# 17_Voltage_Regulators.net
KiCad netlist of a schematic drawn in Altium Designer
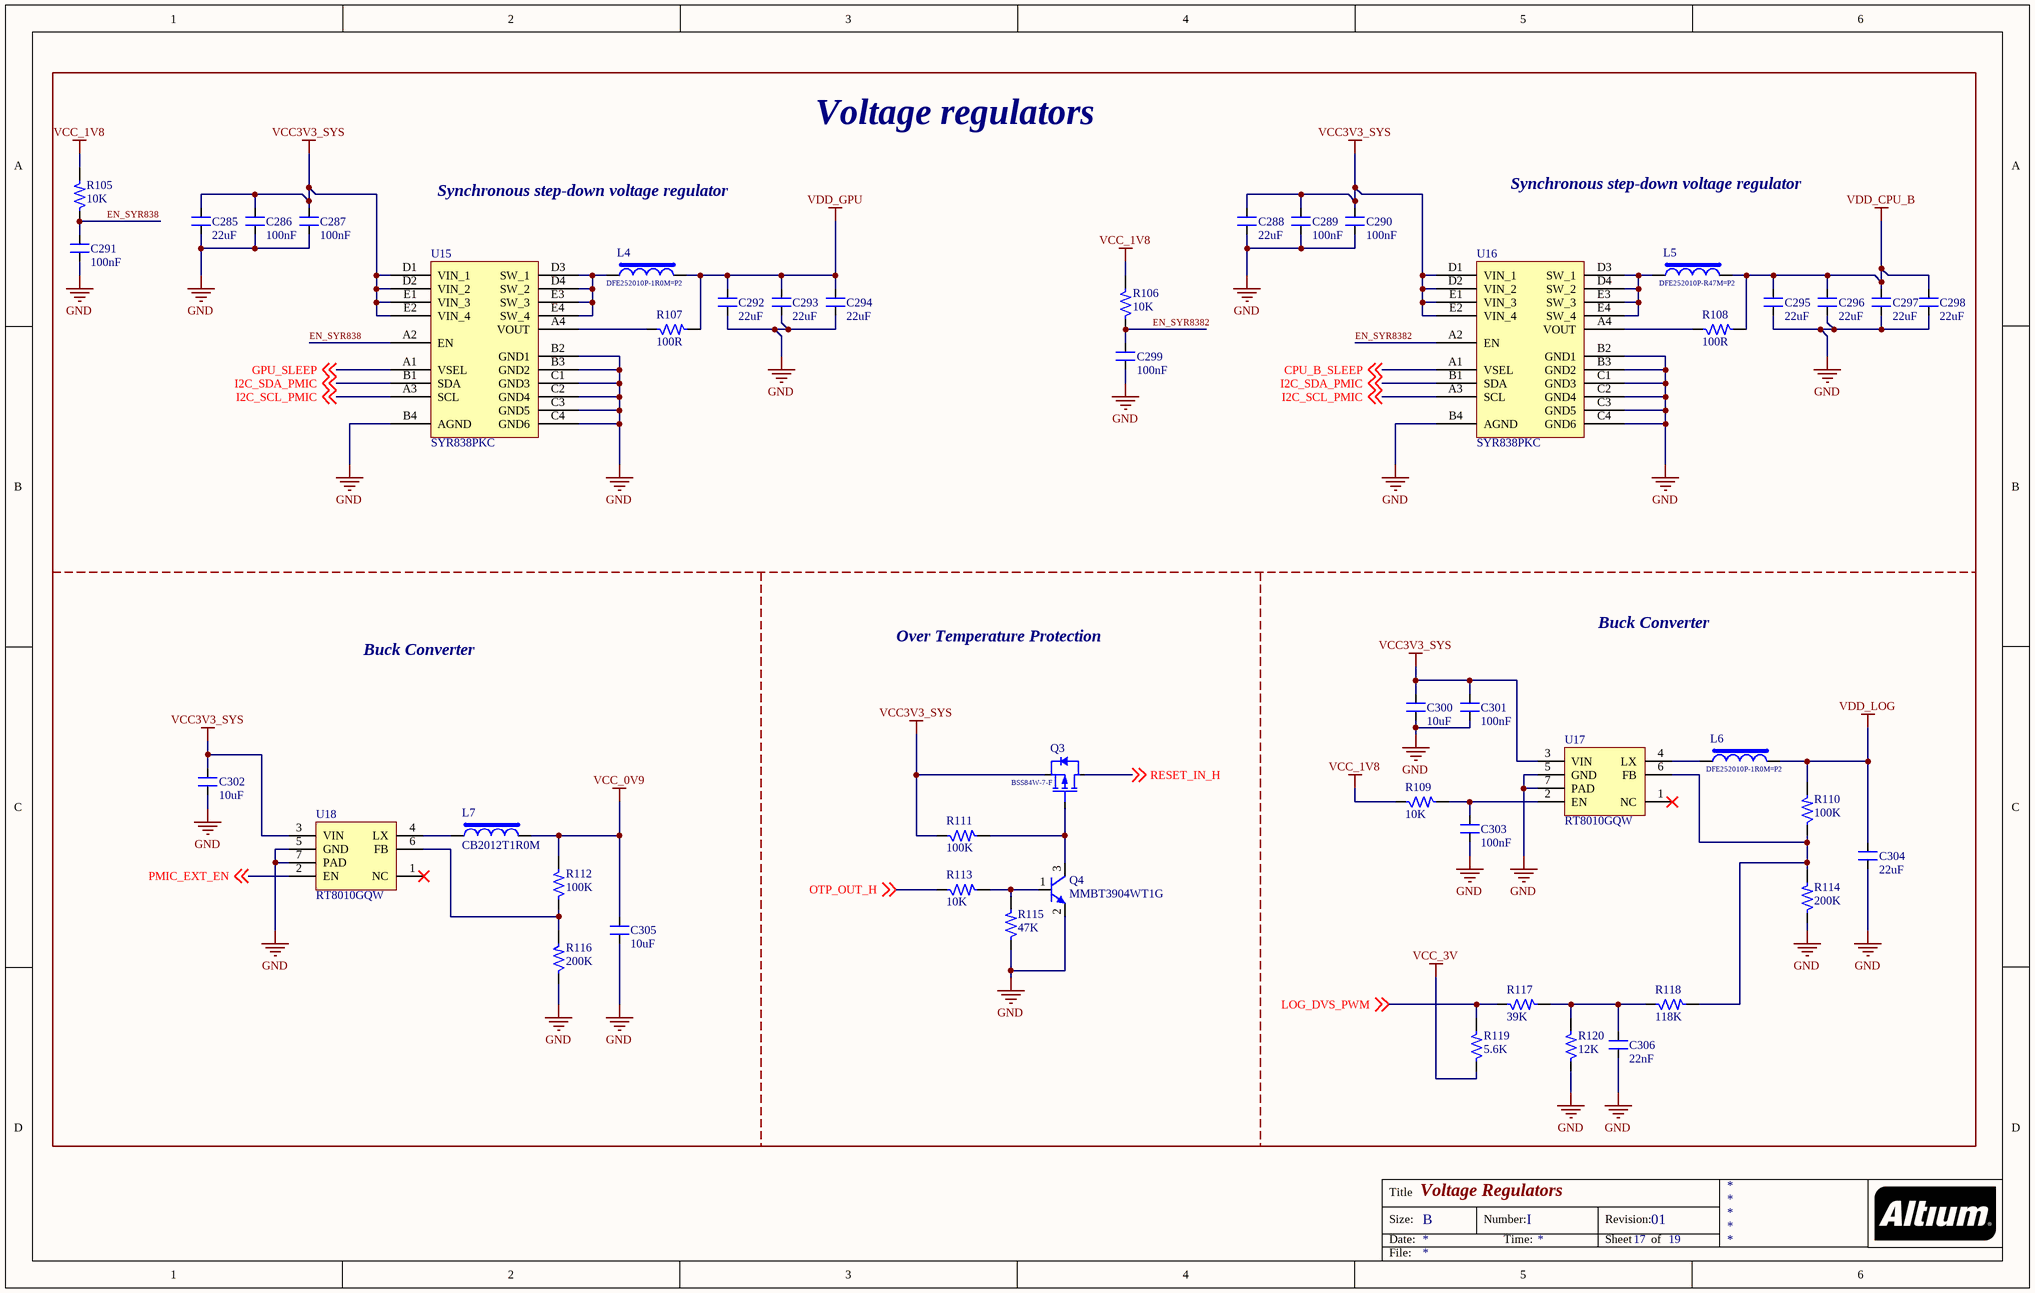
[diagram p0: [17] Voltage_Regulators.SchDoc]

(export (version "E")
  (design (tool "Eeschema 10.0.6"))
  (components
    (comp (ref "C285")
      (value "22uF")
      (footprint "CAP_0402")
      (description "22µF ±20% 6.3V Ceramic Capacitor X5R 0402 (1005 Metric)")
      (fields
        (field (name "MANUFACTURER") "Murata Electronics")
        (field (name "MANUFACTURER PART NUMBER") "CL05A226MQ5N6J8")
      )
      (libsource (lib "EsteemPCB_SOM_Course_intlib") (part "CAP_22uF-6.3V-20%-0402"))
    )
    (comp (ref "C286")
      (value "100nF")
      (footprint "CAP_0402")
      (description "0.1µF ±10% 25V Ceramic Capacitor X7R 0402 (1005 Metric)")
      (fields
        (field (name "MANUFACTURER") "Walsin Technology Corporation")
        (field (name "MANUFACTURER PART NUMBER") "0402B104K250CT")
      )
      (libsource (lib "EsteemPCB_SOM_Course_intlib") (part "CAP_100nF-25V-10%-0402"))
    )
    (comp (ref "C287")
      (value "100nF")
      (footprint "CAP_0402")
      (description "0.1µF ±10% 25V Ceramic Capacitor X7R 0402 (1005 Metric)")
      (fields
        (field (name "MANUFACTURER") "Walsin Technology Corporation")
        (field (name "MANUFACTURER PART NUMBER") "0402B104K250CT")
      )
      (libsource (lib "EsteemPCB_SOM_Course_intlib") (part "CAP_100nF-25V-10%-0402"))
    )
    (comp (ref "C288")
      (value "22uF")
      (footprint "CAP_0402")
      (description "22µF ±20% 6.3V Ceramic Capacitor X5R 0402 (1005 Metric)")
      (fields
        (field (name "MANUFACTURER") "Murata Electronics")
        (field (name "MANUFACTURER PART NUMBER") "CL05A226MQ5N6J8")
      )
      (libsource (lib "EsteemPCB_SOM_Course_intlib") (part "CAP_22uF-6.3V-20%-0402"))
    )
    (comp (ref "C289")
      (value "100nF")
      (footprint "CAP_0402")
      (description "0.1µF ±10% 25V Ceramic Capacitor X7R 0402 (1005 Metric)")
      (fields
        (field (name "MANUFACTURER") "Walsin Technology Corporation")
        (field (name "MANUFACTURER PART NUMBER") "0402B104K250CT")
      )
      (libsource (lib "EsteemPCB_SOM_Course_intlib") (part "CAP_100nF-25V-10%-0402"))
    )
    (comp (ref "C290")
      (value "100nF")
      (footprint "CAP_0402")
      (description "0.1µF ±10% 25V Ceramic Capacitor X7R 0402 (1005 Metric)")
      (fields
        (field (name "MANUFACTURER") "Walsin Technology Corporation")
        (field (name "MANUFACTURER PART NUMBER") "0402B104K250CT")
      )
      (libsource (lib "EsteemPCB_SOM_Course_intlib") (part "CAP_100nF-25V-10%-0402"))
    )
    (comp (ref "C291")
      (value "100nF")
      (footprint "CAP_0402")
      (description "0.1µF ±10% 25V Ceramic Capacitor X7R 0402 (1005 Metric)")
      (fields
        (field (name "MANUFACTURER") "Walsin Technology Corporation")
        (field (name "MANUFACTURER PART NUMBER") "0402B104K250CT")
      )
      (libsource (lib "EsteemPCB_SOM_Course_intlib") (part "CAP_100nF-25V-10%-0402"))
    )
    (comp (ref "C292")
      (value "22uF")
      (footprint "CAP_0402")
      (description "22µF ±20% 6.3V Ceramic Capacitor X5R 0402 (1005 Metric)")
      (fields
        (field (name "MANUFACTURER") "Murata Electronics")
        (field (name "MANUFACTURER PART NUMBER") "CL05A226MQ5N6J8")
      )
      (libsource (lib "EsteemPCB_SOM_Course_intlib") (part "CAP_22uF-6.3V-20%-0402"))
    )
    (comp (ref "C293")
      (value "22uF")
      (footprint "CAP_0402")
      (description "22µF ±20% 6.3V Ceramic Capacitor X5R 0402 (1005 Metric)")
      (fields
        (field (name "MANUFACTURER") "Murata Electronics")
        (field (name "MANUFACTURER PART NUMBER") "CL05A226MQ5N6J8")
      )
      (libsource (lib "EsteemPCB_SOM_Course_intlib") (part "CAP_22uF-6.3V-20%-0402"))
    )
    (comp (ref "C294")
      (value "22uF")
      (footprint "CAP_0402")
      (description "22µF ±20% 6.3V Ceramic Capacitor X5R 0402 (1005 Metric)")
      (fields
        (field (name "MANUFACTURER") "Murata Electronics")
        (field (name "MANUFACTURER PART NUMBER") "CL05A226MQ5N6J8")
      )
      (libsource (lib "EsteemPCB_SOM_Course_intlib") (part "CAP_22uF-6.3V-20%-0402"))
    )
    (comp (ref "C295")
      (value "22uF")
      (footprint "CAP_0402")
      (description "22µF ±20% 6.3V Ceramic Capacitor X5R 0402 (1005 Metric)")
      (fields
        (field (name "MANUFACTURER") "Murata Electronics")
        (field (name "MANUFACTURER PART NUMBER") "CL05A226MQ5N6J8")
      )
      (libsource (lib "EsteemPCB_SOM_Course_intlib") (part "CAP_22uF-6.3V-20%-0402"))
    )
    (comp (ref "C296")
      (value "22uF")
      (footprint "CAP_0402")
      (description "22µF ±20% 6.3V Ceramic Capacitor X5R 0402 (1005 Metric)")
      (fields
        (field (name "MANUFACTURER") "Murata Electronics")
        (field (name "MANUFACTURER PART NUMBER") "CL05A226MQ5N6J8")
      )
      (libsource (lib "EsteemPCB_SOM_Course_intlib") (part "CAP_22uF-6.3V-20%-0402"))
    )
    (comp (ref "C297")
      (value "22uF")
      (footprint "CAP_0402")
      (description "22µF ±20% 6.3V Ceramic Capacitor X5R 0402 (1005 Metric)")
      (fields
        (field (name "MANUFACTURER") "Murata Electronics")
        (field (name "MANUFACTURER PART NUMBER") "CL05A226MQ5N6J8")
      )
      (libsource (lib "EsteemPCB_SOM_Course_intlib") (part "CAP_22uF-6.3V-20%-0402"))
    )
    (comp (ref "C298")
      (value "22uF")
      (footprint "CAP_0402")
      (description "22µF ±20% 6.3V Ceramic Capacitor X5R 0402 (1005 Metric)")
      (fields
        (field (name "MANUFACTURER") "Murata Electronics")
        (field (name "MANUFACTURER PART NUMBER") "CL05A226MQ5N6J8")
      )
      (libsource (lib "EsteemPCB_SOM_Course_intlib") (part "CAP_22uF-6.3V-20%-0402"))
    )
    (comp (ref "C299")
      (value "100nF")
      (footprint "CAP_0402")
      (description "0.1µF ±10% 25V Ceramic Capacitor X7R 0402 (1005 Metric)")
      (fields
        (field (name "MANUFACTURER") "Walsin Technology Corporation")
        (field (name "MANUFACTURER PART NUMBER") "0402B104K250CT")
      )
      (libsource (lib "EsteemPCB_SOM_Course_intlib") (part "CAP_100nF-25V-10%-0402"))
    )
    (comp (ref "C300")
      (value "10uF")
      (footprint "CAP_0402")
      (description "10µF ±20% 10V Ceramic Capacitor X5R 0402 (1005 Metric)")
      (fields
        (field (name "MANUFACTURER PART NUMBER") "CL05A106MP5NUNC")
        (field (name "MANUFACTURER") "Samsung Electro-Mechanics")
      )
      (libsource (lib "EsteemPCB_SOM_Course_intlib") (part "CAP_10uF-10V-20%-0402"))
    )
    (comp (ref "C301")
      (value "100nF")
      (footprint "CAP_0402")
      (description "0.1µF ±10% 10V Ceramic Capacitor X7R 0402 (1005 Metric)")
      (fields
        (field (name "MANUFACTURER") "Yageo")
        (field (name "MANUFACTURER PART NUMBER") "CC0402KRX7R6BB104")
      )
      (libsource (lib "EsteemPCB_SOM_Course_intlib") (part "CAP_100nF-10V-10%-0402"))
    )
    (comp (ref "C302")
      (value "10uF")
      (footprint "CAP_0402")
      (description "10µF ±20% 10V Ceramic Capacitor X5R 0402 (1005 Metric)")
      (fields
        (field (name "MANUFACTURER PART NUMBER") "CL05A106MP5NUNC")
        (field (name "MANUFACTURER") "Samsung Electro-Mechanics")
      )
      (libsource (lib "EsteemPCB_SOM_Course_intlib") (part "CAP_10uF-10V-20%-0402"))
    )
    (comp (ref "C303")
      (value "100nF")
      (footprint "CAP_0402")
      (description "0.1µF ±10% 10V Ceramic Capacitor X7R 0402 (1005 Metric)")
      (fields
        (field (name "MANUFACTURER") "Yageo")
        (field (name "MANUFACTURER PART NUMBER") "CC0402KRX7R6BB104")
      )
      (libsource (lib "EsteemPCB_SOM_Course_intlib") (part "CAP_100nF-10V-10%-0402"))
    )
    (comp (ref "C304")
      (value "22uF")
      (footprint "CAP_0402")
      (description "22µF ±20% 6.3V Ceramic Capacitor X5R 0402 (1005 Metric)")
      (fields
        (field (name "MANUFACTURER") "Murata Electronics")
        (field (name "MANUFACTURER PART NUMBER") "CL05A226MQ5N6J8")
      )
      (libsource (lib "EsteemPCB_SOM_Course_intlib") (part "CAP_22uF-6.3V-20%-0402"))
    )
    (comp (ref "C305")
      (value "10uF")
      (footprint "CAP_0402")
      (description "10µF ±20% 10V Ceramic Capacitor X5R 0402 (1005 Metric)")
      (fields
        (field (name "MANUFACTURER PART NUMBER") "CL05A106MP5NUNC")
        (field (name "MANUFACTURER") "Samsung Electro-Mechanics")
      )
      (libsource (lib "EsteemPCB_SOM_Course_intlib") (part "CAP_10uF-10V-20%-0402"))
    )
    (comp (ref "C306")
      (value "22nF")
      (footprint "CAP_0402")
      (description "0.022µF ±10% 10V Ceramic Capacitor X7R 0402 (1005 Metric)")
      (fields
        (field (name "MANUFACTURER") "Samsung Electro-Mechanics")
        (field (name "MANUFACTURER PART NUMBER") "CL05B223KP5NNNC")
      )
      (libsource (lib "EsteemPCB_SOM_Course_intlib") (part "CAP_22nF-10V-10%-0402"))
    )
    (comp (ref "L4")
      (value "DFE252010P-1R0M=P2")
      (footprint "IND_1008")
      (description "1µH Shielded Wirewound Inductor 3.8A 54mOhm Max 1008 (2520 Metric)")
      (fields (field (name "MANUFACTURER") "Murata Electronics"))
      (libsource (lib "EsteemPCB_SOM_Course_intlib") (part "IND_1uH-3.8A-20%-1008"))
    )
    (comp (ref "L5")
      (value "DFE252010P-R47M=P2")
      (footprint "IND_1008")
      (description "470nH Shielded Wirewound Inductor 5A 35mOhm Max 1008 (2520 Metric)")
      (fields (field (name "MANUFACTURER") "Murata Electronics"))
      (libsource (lib "EsteemPCB_SOM_Course_intlib") (part "IND_470nH-5A-20%-1008"))
    )
    (comp (ref "L6")
      (value "DFE252010P-1R0M=P2")
      (footprint "IND_1008")
      (description "1µH Shielded Wirewound Inductor 3.8A 54mOhm Max 1008 (2520 Metric)")
      (fields (field (name "MANUFACTURER") "Murata Electronics"))
      (libsource (lib "EsteemPCB_SOM_Course_intlib") (part "IND_1uH-3.8A-20%-1008"))
    )
    (comp (ref "L7")
      (value "CB2012T1R0M")
      (footprint "IND_0805")
      (description "1uH ±20% 500mA 150mΩ 0805 Inductors (SMD) RoHS")
      (fields (field (name "MANUFACTURER") "Taiyo Yuden"))
      (libsource (lib "EsteemPCB_SOM_Course_intlib") (part "IND_1uF-0.5A-20%-0805"))
    )
    (comp (ref "Q3")
      (value "BSS84W-7-F")
      (footprint "SOT-323-3")
      (description "P-Channel 50V 130mA (Ta) 200mW (Ta) Surface Mount SOT-323")
      (fields (field (name "MANUFACTURER") "Diodes Incorporated"))
      (libsource (lib "EsteemPCB_SOM_Course_intlib") (part "MOSFET-P_50V-130mA-SOT-323"))
    )
    (comp (ref "Q4")
      (value "MMBT3904WT1G")
      (footprint "SOT-323-3")
      (description "Bipolar (BJT) Transistor NPN 40V 200mA 300MHz 150mW Surface Mount SC-70-3 (SOT323)")
      (fields (field (name "MANUFACTURER") "ON Semiconductor"))
      (libsource (lib "EsteemPCB_SOM_Course_intlib") (part "TRAN-NPN_40V-200mA-SOT323"))
    )
    (comp (ref "R105")
      (value "10K")
      (footprint "RES_0402")
      (description "10 kOhms ±1% 0.1W, 1/10W Chip Resistor 0402 (1005 Metric) Anti-Sulfur Thin Film")
      (fields
        (field (name "MANUFACTURER") "Vishay Beyschlag/Draloric/BC Components")
        (field (name "MANUFACTURER PART NUMBER") "MCS04020C1002FE000")
      )
      (libsource (lib "EsteemPCB_SOM_Course_intlib") (part "RES_10K-0.1W-1%-0402"))
    )
    (comp (ref "R106")
      (value "10K")
      (footprint "RES_0402")
      (description "10 kOhms ±1% 0.1W, 1/10W Chip Resistor 0402 (1005 Metric) Anti-Sulfur Thin Film")
      (fields
        (field (name "MANUFACTURER") "Vishay Beyschlag/Draloric/BC Components")
        (field (name "MANUFACTURER PART NUMBER") "MCS04020C1002FE000")
      )
      (libsource (lib "EsteemPCB_SOM_Course_intlib") (part "RES_10K-0.1W-1%-0402"))
    )
    (comp (ref "R107")
      (value "100R")
      (footprint "RES_0402")
      (fields
        (field (name "MANUFACTURER") "KOA Speer Electronics, Inc.")
        (field (name "MANUFACTURER PART NUMBER") "RK73H1ETTP1000F")
      )
      (libsource (lib "EsteemPCB_SOM_Course_intlib") (part "RES_100R-0.1W-1%-0402"))
    )
    (comp (ref "R108")
      (value "100R")
      (footprint "RES_0402")
      (fields
        (field (name "MANUFACTURER") "KOA Speer Electronics, Inc.")
        (field (name "MANUFACTURER PART NUMBER") "RK73H1ETTP1000F")
      )
      (libsource (lib "EsteemPCB_SOM_Course_intlib") (part "RES_100R-0.1W-1%-0402"))
    )
    (comp (ref "R109")
      (value "10K")
      (footprint "RES_0402")
      (description "10 kOhms ±1% 0.1W, 1/10W Chip Resistor 0402 (1005 Metric) Anti-Sulfur Thin Film")
      (fields
        (field (name "MANUFACTURER") "Vishay Beyschlag/Draloric/BC Components")
        (field (name "MANUFACTURER PART NUMBER") "MCS04020C1002FE000")
      )
      (libsource (lib "EsteemPCB_SOM_Course_intlib") (part "RES_10K-0.1W-1%-0402"))
    )
    (comp (ref "R110")
      (value "100K")
      (footprint "RES_0402")
      (description "100 kOhms ±1% 0.1W, 1/10W Chip Resistor 0402 (1005 Metric) Anti-Sulfur Thin Film")
      (fields
        (field (name "MANUFACTURER") "Vishay Beyschlag/Draloric/BC Components")
        (field (name "MANUFACTURER PART NUMBER") "MCS04020C1003FE000")
      )
      (libsource (lib "EsteemPCB_SOM_Course_intlib") (part "RES_100K-0.1W-1%-0402"))
    )
    (comp (ref "R111")
      (value "100K")
      (footprint "RES_0402")
      (description "100 kOhms ±1% 0.1W, 1/10W Chip Resistor 0402 (1005 Metric) Anti-Sulfur Thin Film")
      (fields
        (field (name "MANUFACTURER") "Vishay Beyschlag/Draloric/BC Components")
        (field (name "MANUFACTURER PART NUMBER") "MCS04020C1003FE000")
      )
      (libsource (lib "EsteemPCB_SOM_Course_intlib") (part "RES_100K-0.1W-1%-0402"))
    )
    (comp (ref "R112")
      (value "100K")
      (footprint "RES_0402")
      (description "100 kOhms ±1% 0.1W, 1/10W Chip Resistor 0402 (1005 Metric) Anti-Sulfur Thin Film")
      (fields
        (field (name "MANUFACTURER") "Vishay Beyschlag/Draloric/BC Components")
        (field (name "MANUFACTURER PART NUMBER") "MCS04020C1003FE000")
      )
      (libsource (lib "EsteemPCB_SOM_Course_intlib") (part "RES_100K-0.1W-1%-0402"))
    )
    (comp (ref "R113")
      (value "10K")
      (footprint "RES_0402")
      (description "10 kOhms ±1% 0.1W, 1/10W Chip Resistor 0402 (1005 Metric) Anti-Sulfur Thin Film")
      (fields
        (field (name "MANUFACTURER") "Vishay Beyschlag/Draloric/BC Components")
        (field (name "MANUFACTURER PART NUMBER") "MCS04020C1002FE000")
      )
      (libsource (lib "EsteemPCB_SOM_Course_intlib") (part "RES_10K-0.1W-1%-0402"))
    )
    (comp (ref "R114")
      (value "200K")
      (footprint "RES_0402")
      (description "200 kOhms ±1% 0.1W, 1/10W Chip Resistor 0402 (1005 Metric) Automotive AEC-Q200 Thick Film")
      (fields
        (field (name "MANUFACTURER") "Panasonic Electronic Components")
        (field (name "MANUFACTURER PART NUMBER") "ERJ-2RKF2003X")
      )
      (libsource (lib "EsteemPCB_SOM_Course_intlib") (part "RES_200K-0.1W-1%-0402"))
    )
    (comp (ref "R115")
      (value "47K")
      (footprint "RES_0402")
      (description "47 kOhms ±1% 0.1W, 1/10W Chip Resistor 0402 (1005 Metric) Automotive AEC-Q200 Thick Film")
      (fields
        (field (name "MANUFACTURER") "Panasonic Electronic Components")
        (field (name "MANUFACTURER PART NUMBER") "ERJ-2RKF4702X")
      )
      (libsource (lib "EsteemPCB_SOM_Course_intlib") (part "RES_47K-0.1W-1%-0402"))
    )
    (comp (ref "R116")
      (value "200K")
      (footprint "RES_0402")
      (description "200 kOhms ±1% 0.1W, 1/10W Chip Resistor 0402 (1005 Metric) Automotive AEC-Q200 Thick Film")
      (fields
        (field (name "MANUFACTURER") "Panasonic Electronic Components")
        (field (name "MANUFACTURER PART NUMBER") "ERJ-2RKF2003X")
      )
      (libsource (lib "EsteemPCB_SOM_Course_intlib") (part "RES_200K-0.1W-1%-0402"))
    )
    (comp (ref "R117")
      (value "39K")
      (footprint "RES_0402")
      (fields
        (field (name "MANUFACTURER") "KOA Speer Electronics, Inc.")
        (field (name "MANUFACTURER PART NUMBER") "RK73H1ETTP3902F")
      )
      (libsource (lib "EsteemPCB_SOM_Course_intlib") (part "RES_39K-0.1W-1%-0402"))
    )
    (comp (ref "R118")
      (value "118K")
      (footprint "RES_0402")
      (fields
        (field (name "MANUFACTURER") "KOA Speer Electronics, Inc.")
        (field (name "MANUAFCTURER PART NUMBER") "RK73H1ETTP1183F")
      )
      (libsource (lib "EsteemPCB_SOM_Course_intlib") (part "RES_118K-0.1W-1%-0402"))
    )
    (comp (ref "R119")
      (value "5.6K")
      (footprint "RES_0402")
      (fields
        (field (name "MANUFACTURER") "KOA Speer Electronics, Inc.")
        (field (name "MANUFACTURER PART NUMBER") "RK73H1ETTP5601F")
      )
      (libsource (lib "EsteemPCB_SOM_Course_intlib") (part "RES_5.6K-0.1W-1%-0402"))
    )
    (comp (ref "R120")
      (value "12K")
      (footprint "RES_0402")
      (description "12 kOhms ±1% 0.1W, 1/10W Chip Resistor 0402 (1005 Metric) Anti-Sulfur Thin Film")
      (fields
        (field (name "MANUFACTURER") "Vishay Beyschlag/Draloric/BC Components")
        (field (name "MANUFACTURER PART NUMBER") "MCS04020C1202FE000")
      )
      (libsource (lib "EsteemPCB_SOM_Course_intlib") (part "RES_12K-0.1W-1%-0402"))
    )
    (comp (ref "U15")
      (value "SYR838PKC")
      (footprint "CSP20_15.7_100x84_SMD")
      (description "Step-Down Positive Programmable 1 6A 2.4MHz CSP1.56*1.96-20 DC-DC Converters RoHS")
      (fields (field (name "MANUFACTURER") "Silergy Corp"))
      (libsource (lib "EsteemPCB_SOM_Course_intlib") (part "IC_SYR838PKC"))
    )
    (comp (ref "U16")
      (value "SYR838PKC")
      (footprint "CSP20_15.7_100x84_SMD")
      (description "Step-Down Positive Programmable 1 6A 2.4MHz CSP1.56*1.96-20 DC-DC Converters RoHS")
      (fields (field (name "MANUFACTURER") "Silergy Corp"))
      (libsource (lib "EsteemPCB_SOM_Course_intlib") (part "IC_SYR838PKC"))
    )
    (comp (ref "U17")
      (value "RT8010GQW")
      (footprint "WDFN-6_26_133X100_SMD")
      (description "Buck Switching Regulator IC Positive Adjustable 0.6V 1 Output 1A 6-WDFN Exposed Pad")
      (fields (field (name "MANUFACTURER") "Richtek USA Inc."))
      (libsource (lib "EsteemPCB_SOM_Course_intlib") (part "REG-ADJ_5.5V-5.5V-1A-6-WDFN"))
    )
    (comp (ref "U18")
      (value "RT8010GQW")
      (footprint "WDFN-6_26_133X100_SMD")
      (description "Buck Switching Regulator IC Positive Adjustable 0.6V 1 Output 1A 6-WDFN Exposed Pad")
      (fields (field (name "MANUFACTURER") "Richtek USA Inc."))
      (libsource (lib "EsteemPCB_SOM_Course_intlib") (part "REG-ADJ_5.5V-5.5V-1A-6-WDFN"))
    )
  )
  (nets
    (net (code "1") (name "/EN_SYR838") (class "Default")
      (node (ref "C291") (pin "2") (pinfunction "2_2") (pintype "passive"))
      (node (ref "R105") (pin "1") (pinfunction "1_1") (pintype "passive"))
      (node (ref "U15") (pin "A2") (pinfunction "EN_A2") (pintype "passive"))
    )
    (net (code "2") (name "/EN_SYR8382") (class "Default")
      (node (ref "C299") (pin "2") (pinfunction "2_2") (pintype "passive"))
      (node (ref "R106") (pin "1") (pinfunction "1_1") (pintype "passive"))
      (node (ref "U16") (pin "A2") (pinfunction "EN_A2") (pintype "passive"))
    )
    (net (code "3") (name "CPU_B_SLEEP") (class "Default")
      (node (ref "U16") (pin "A1") (pinfunction "VSEL_A1") (pintype "passive"))
    )
    (net (code "4") (name "GND") (class "Default")
      (node (ref "C285") (pin "1") (pinfunction "1_1") (pintype "passive"))
      (node (ref "C286") (pin "1") (pinfunction "1_1") (pintype "passive"))
      (node (ref "C287") (pin "1") (pinfunction "1_1") (pintype "passive"))
      (node (ref "C288") (pin "1") (pinfunction "1_1") (pintype "passive"))
      (node (ref "C289") (pin "1") (pinfunction "1_1") (pintype "passive"))
      (node (ref "C290") (pin "1") (pinfunction "1_1") (pintype "passive"))
      (node (ref "C291") (pin "1") (pinfunction "1_1") (pintype "passive"))
      (node (ref "C292") (pin "1") (pinfunction "1_1") (pintype "passive"))
      (node (ref "C293") (pin "1") (pinfunction "1_1") (pintype "passive"))
      (node (ref "C294") (pin "1") (pinfunction "1_1") (pintype "passive"))
      (node (ref "C295") (pin "1") (pinfunction "1_1") (pintype "passive"))
      (node (ref "C296") (pin "1") (pinfunction "1_1") (pintype "passive"))
      (node (ref "C297") (pin "1") (pinfunction "1_1") (pintype "passive"))
      (node (ref "C298") (pin "1") (pinfunction "1_1") (pintype "passive"))
      (node (ref "C299") (pin "1") (pinfunction "1_1") (pintype "passive"))
      (node (ref "C300") (pin "1") (pinfunction "1_1") (pintype "passive"))
      (node (ref "C301") (pin "1") (pinfunction "1_1") (pintype "passive"))
      (node (ref "C302") (pin "1") (pinfunction "1_1") (pintype "passive"))
      (node (ref "C303") (pin "1") (pinfunction "1_1") (pintype "passive"))
      (node (ref "C304") (pin "1") (pinfunction "1_1") (pintype "passive"))
      (node (ref "C305") (pin "1") (pinfunction "1_1") (pintype "passive"))
      (node (ref "C306") (pin "1") (pinfunction "1_1") (pintype "passive"))
      (node (ref "Q4") (pin "2") (pinfunction "E_2") (pintype "passive"))
      (node (ref "R114") (pin "1") (pinfunction "1_1") (pintype "passive"))
      (node (ref "R115") (pin "1") (pinfunction "1_1") (pintype "passive"))
      (node (ref "R116") (pin "1") (pinfunction "1_1") (pintype "passive"))
      (node (ref "R120") (pin "1") (pinfunction "1_1") (pintype "passive"))
      (node (ref "U15") (pin "B2") (pinfunction "GND1_B2") (pintype "passive"))
      (node (ref "U15") (pin "B3") (pinfunction "GND2_B3") (pintype "passive"))
      (node (ref "U15") (pin "B4") (pinfunction "AGND_B4") (pintype "passive"))
      (node (ref "U15") (pin "C1") (pinfunction "GND3_C1") (pintype "passive"))
      (node (ref "U15") (pin "C2") (pinfunction "GND4_C2") (pintype "passive"))
      (node (ref "U15") (pin "C3") (pinfunction "GND5_C3") (pintype "passive"))
      (node (ref "U15") (pin "C4") (pinfunction "GND6_C4") (pintype "passive"))
      (node (ref "U16") (pin "B2") (pinfunction "GND1_B2") (pintype "passive"))
      (node (ref "U16") (pin "B3") (pinfunction "GND2_B3") (pintype "passive"))
      (node (ref "U16") (pin "B4") (pinfunction "AGND_B4") (pintype "passive"))
      (node (ref "U16") (pin "C1") (pinfunction "GND3_C1") (pintype "passive"))
      (node (ref "U16") (pin "C2") (pinfunction "GND4_C2") (pintype "passive"))
      (node (ref "U16") (pin "C3") (pinfunction "GND5_C3") (pintype "passive"))
      (node (ref "U16") (pin "C4") (pinfunction "GND6_C4") (pintype "passive"))
      (node (ref "U17") (pin "5") (pinfunction "GND_5") (pintype "passive"))
      (node (ref "U17") (pin "7") (pinfunction "PAD_7") (pintype "passive"))
      (node (ref "U18") (pin "5") (pinfunction "GND_5") (pintype "passive"))
      (node (ref "U18") (pin "7") (pinfunction "PAD_7") (pintype "passive"))
    )
    (net (code "5") (name "GPU_SLEEP") (class "Default")
      (node (ref "U15") (pin "A1") (pinfunction "VSEL_A1") (pintype "passive"))
    )
    (net (code "6") (name "I2C_SCL_PMIC") (class "Default")
      (node (ref "U15") (pin "A3") (pinfunction "SCL_A3") (pintype "passive"))
      (node (ref "U16") (pin "A3") (pinfunction "SCL_A3") (pintype "passive"))
    )
    (net (code "7") (name "I2C_SDA_PMIC") (class "Default")
      (node (ref "U15") (pin "B1") (pinfunction "SDA_B1") (pintype "passive"))
      (node (ref "U16") (pin "B1") (pinfunction "SDA_B1") (pintype "passive"))
    )
    (net (code "8") (name "LOG_DVS_PWM") (class "Default")
      (node (ref "R117") (pin "1") (pinfunction "1_1") (pintype "passive"))
      (node (ref "R119") (pin "2") (pinfunction "2_2") (pintype "passive"))
    )
    (net (code "9") (name "Net-(C306-Pad2)") (class "Default")
      (node (ref "C306") (pin "2") (pinfunction "2_2") (pintype "passive"))
      (node (ref "R117") (pin "2") (pinfunction "2_2") (pintype "passive"))
      (node (ref "R118") (pin "1") (pinfunction "1_1") (pintype "passive"))
      (node (ref "R120") (pin "2") (pinfunction "2_2") (pintype "passive"))
    )
    (net (code "10") (name "Net-(Q3-G)") (class "Default")
      (node (ref "Q3") (pin "1") (pinfunction "G_1") (pintype "passive"))
      (node (ref "Q4") (pin "3") (pinfunction "C_3") (pintype "passive"))
      (node (ref "R111") (pin "2") (pinfunction "2_2") (pintype "passive"))
    )
    (net (code "11") (name "Net-(Q4-B)") (class "Default")
      (node (ref "Q4") (pin "1") (pinfunction "B_1") (pintype "passive"))
      (node (ref "R113") (pin "2") (pinfunction "2_2") (pintype "passive"))
      (node (ref "R115") (pin "2") (pinfunction "2_2") (pintype "passive"))
    )
    (net (code "12") (name "Net-(U15-SW_1)") (class "Default")
      (node (ref "L4") (pin "1") (pinfunction "1_1") (pintype "passive"))
      (node (ref "U15") (pin "D3") (pinfunction "SW_1_D3") (pintype "passive"))
      (node (ref "U15") (pin "D4") (pinfunction "SW_2_D4") (pintype "passive"))
      (node (ref "U15") (pin "E3") (pinfunction "SW_3_E3") (pintype "passive"))
      (node (ref "U15") (pin "E4") (pinfunction "SW_4_E4") (pintype "passive"))
    )
    (net (code "13") (name "Net-(U15-VOUT)") (class "Default")
      (node (ref "R107") (pin "1") (pinfunction "1_1") (pintype "passive"))
      (node (ref "U15") (pin "A4") (pinfunction "VOUT_A4") (pintype "passive"))
    )
    (net (code "14") (name "Net-(U16-SW_1)") (class "Default")
      (node (ref "L5") (pin "1") (pinfunction "1_1") (pintype "passive"))
      (node (ref "U16") (pin "D3") (pinfunction "SW_1_D3") (pintype "passive"))
      (node (ref "U16") (pin "D4") (pinfunction "SW_2_D4") (pintype "passive"))
      (node (ref "U16") (pin "E3") (pinfunction "SW_3_E3") (pintype "passive"))
      (node (ref "U16") (pin "E4") (pinfunction "SW_4_E4") (pintype "passive"))
    )
    (net (code "15") (name "Net-(U16-VOUT)") (class "Default")
      (node (ref "R108") (pin "1") (pinfunction "1_1") (pintype "passive"))
      (node (ref "U16") (pin "A4") (pinfunction "VOUT_A4") (pintype "passive"))
    )
    (net (code "16") (name "Net-(U17-EN)") (class "Default")
      (node (ref "C303") (pin "2") (pinfunction "2_2") (pintype "passive"))
      (node (ref "R109") (pin "2") (pinfunction "2_2") (pintype "passive"))
      (node (ref "U17") (pin "2") (pinfunction "EN_2") (pintype "passive"))
    )
    (net (code "17") (name "Net-(U17-FB)") (class "Default")
      (node (ref "R110") (pin "1") (pinfunction "1_1") (pintype "passive"))
      (node (ref "R114") (pin "2") (pinfunction "2_2") (pintype "passive"))
      (node (ref "R118") (pin "2") (pinfunction "2_2") (pintype "passive"))
      (node (ref "U17") (pin "6") (pinfunction "FB_6") (pintype "passive"))
    )
    (net (code "18") (name "Net-(U17-LX)") (class "Default")
      (node (ref "L6") (pin "1") (pinfunction "1_1") (pintype "passive"))
      (node (ref "U17") (pin "4") (pinfunction "LX_4") (pintype "passive"))
    )
    (net (code "19") (name "Net-(U18-FB)") (class "Default")
      (node (ref "R112") (pin "1") (pinfunction "1_1") (pintype "passive"))
      (node (ref "R116") (pin "2") (pinfunction "2_2") (pintype "passive"))
      (node (ref "U18") (pin "6") (pinfunction "FB_6") (pintype "passive"))
    )
    (net (code "20") (name "Net-(U18-LX)") (class "Default")
      (node (ref "L7") (pin "1") (pinfunction "1_1") (pintype "passive"))
      (node (ref "U18") (pin "4") (pinfunction "LX_4") (pintype "passive"))
    )
    (net (code "21") (name "OTP_OUT_H") (class "Default")
      (node (ref "R113") (pin "1") (pinfunction "1_1") (pintype "passive"))
    )
    (net (code "22") (name "PMIC_EXT_EN") (class "Default")
      (node (ref "U18") (pin "2") (pinfunction "EN_2") (pintype "passive"))
    )
    (net (code "23") (name "RESET_IN_H") (class "Default")
      (node (ref "Q3") (pin "3") (pinfunction "D_3") (pintype "passive"))
    )
    (net (code "24") (name "VCC3V3_SYS") (class "Default")
      (node (ref "C285") (pin "2") (pinfunction "2_2") (pintype "passive"))
      (node (ref "C286") (pin "2") (pinfunction "2_2") (pintype "passive"))
      (node (ref "C287") (pin "2") (pinfunction "2_2") (pintype "passive"))
      (node (ref "C288") (pin "2") (pinfunction "2_2") (pintype "passive"))
      (node (ref "C289") (pin "2") (pinfunction "2_2") (pintype "passive"))
      (node (ref "C290") (pin "2") (pinfunction "2_2") (pintype "passive"))
      (node (ref "C300") (pin "2") (pinfunction "2_2") (pintype "passive"))
      (node (ref "C301") (pin "2") (pinfunction "2_2") (pintype "passive"))
      (node (ref "C302") (pin "2") (pinfunction "2_2") (pintype "passive"))
      (node (ref "Q3") (pin "2") (pinfunction "S_2") (pintype "passive"))
      (node (ref "R111") (pin "1") (pinfunction "1_1") (pintype "passive"))
      (node (ref "U15") (pin "D1") (pinfunction "VIN_1_D1") (pintype "passive"))
      (node (ref "U15") (pin "D2") (pinfunction "VIN_2_D2") (pintype "passive"))
      (node (ref "U15") (pin "E1") (pinfunction "VIN_3_E1") (pintype "passive"))
      (node (ref "U15") (pin "E2") (pinfunction "VIN_4_E2") (pintype "passive"))
      (node (ref "U16") (pin "D1") (pinfunction "VIN_1_D1") (pintype "passive"))
      (node (ref "U16") (pin "D2") (pinfunction "VIN_2_D2") (pintype "passive"))
      (node (ref "U16") (pin "E1") (pinfunction "VIN_3_E1") (pintype "passive"))
      (node (ref "U16") (pin "E2") (pinfunction "VIN_4_E2") (pintype "passive"))
      (node (ref "U17") (pin "3") (pinfunction "VIN_3") (pintype "passive"))
      (node (ref "U18") (pin "3") (pinfunction "VIN_3") (pintype "passive"))
    )
    (net (code "25") (name "VCC_0V9") (class "Default")
      (node (ref "C305") (pin "2") (pinfunction "2_2") (pintype "passive"))
      (node (ref "L7") (pin "2") (pinfunction "2_2") (pintype "passive"))
      (node (ref "R112") (pin "2") (pinfunction "2_2") (pintype "passive"))
    )
    (net (code "26") (name "VCC_1V8") (class "Default")
      (node (ref "R105") (pin "2") (pinfunction "2_2") (pintype "passive"))
      (node (ref "R106") (pin "2") (pinfunction "2_2") (pintype "passive"))
      (node (ref "R109") (pin "1") (pinfunction "1_1") (pintype "passive"))
    )
    (net (code "27") (name "VCC_3V") (class "Default")
      (node (ref "R119") (pin "1") (pinfunction "1_1") (pintype "passive"))
    )
    (net (code "28") (name "VDD_CPU_B") (class "Default")
      (node (ref "C295") (pin "2") (pinfunction "2_2") (pintype "passive"))
      (node (ref "C296") (pin "2") (pinfunction "2_2") (pintype "passive"))
      (node (ref "C297") (pin "2") (pinfunction "2_2") (pintype "passive"))
      (node (ref "C298") (pin "2") (pinfunction "2_2") (pintype "passive"))
      (node (ref "L5") (pin "2") (pinfunction "2_2") (pintype "passive"))
      (node (ref "R108") (pin "2") (pinfunction "2_2") (pintype "passive"))
    )
    (net (code "29") (name "VDD_GPU") (class "Default")
      (node (ref "C292") (pin "2") (pinfunction "2_2") (pintype "passive"))
      (node (ref "C293") (pin "2") (pinfunction "2_2") (pintype "passive"))
      (node (ref "C294") (pin "2") (pinfunction "2_2") (pintype "passive"))
      (node (ref "L4") (pin "2") (pinfunction "2_2") (pintype "passive"))
      (node (ref "R107") (pin "2") (pinfunction "2_2") (pintype "passive"))
    )
    (net (code "30") (name "VDD_LOG") (class "Default")
      (node (ref "C304") (pin "2") (pinfunction "2_2") (pintype "passive"))
      (node (ref "L6") (pin "2") (pinfunction "2_2") (pintype "passive"))
      (node (ref "R110") (pin "2") (pinfunction "2_2") (pintype "passive"))
    )
    (net (code "31") (name "unconnected-(U17-NC-Pad1)") (class "Default")
      (node (ref "U17") (pin "1") (pinfunction "NC_1") (pintype "passive+no_connect"))
    )
    (net (code "32") (name "unconnected-(U18-NC-Pad1)") (class "Default")
      (node (ref "U18") (pin "1") (pinfunction "NC_1") (pintype "passive+no_connect"))
    )
  )
)
